# 3V3_MCU.net
KiCad netlist of a schematic drawn in Altium Designer
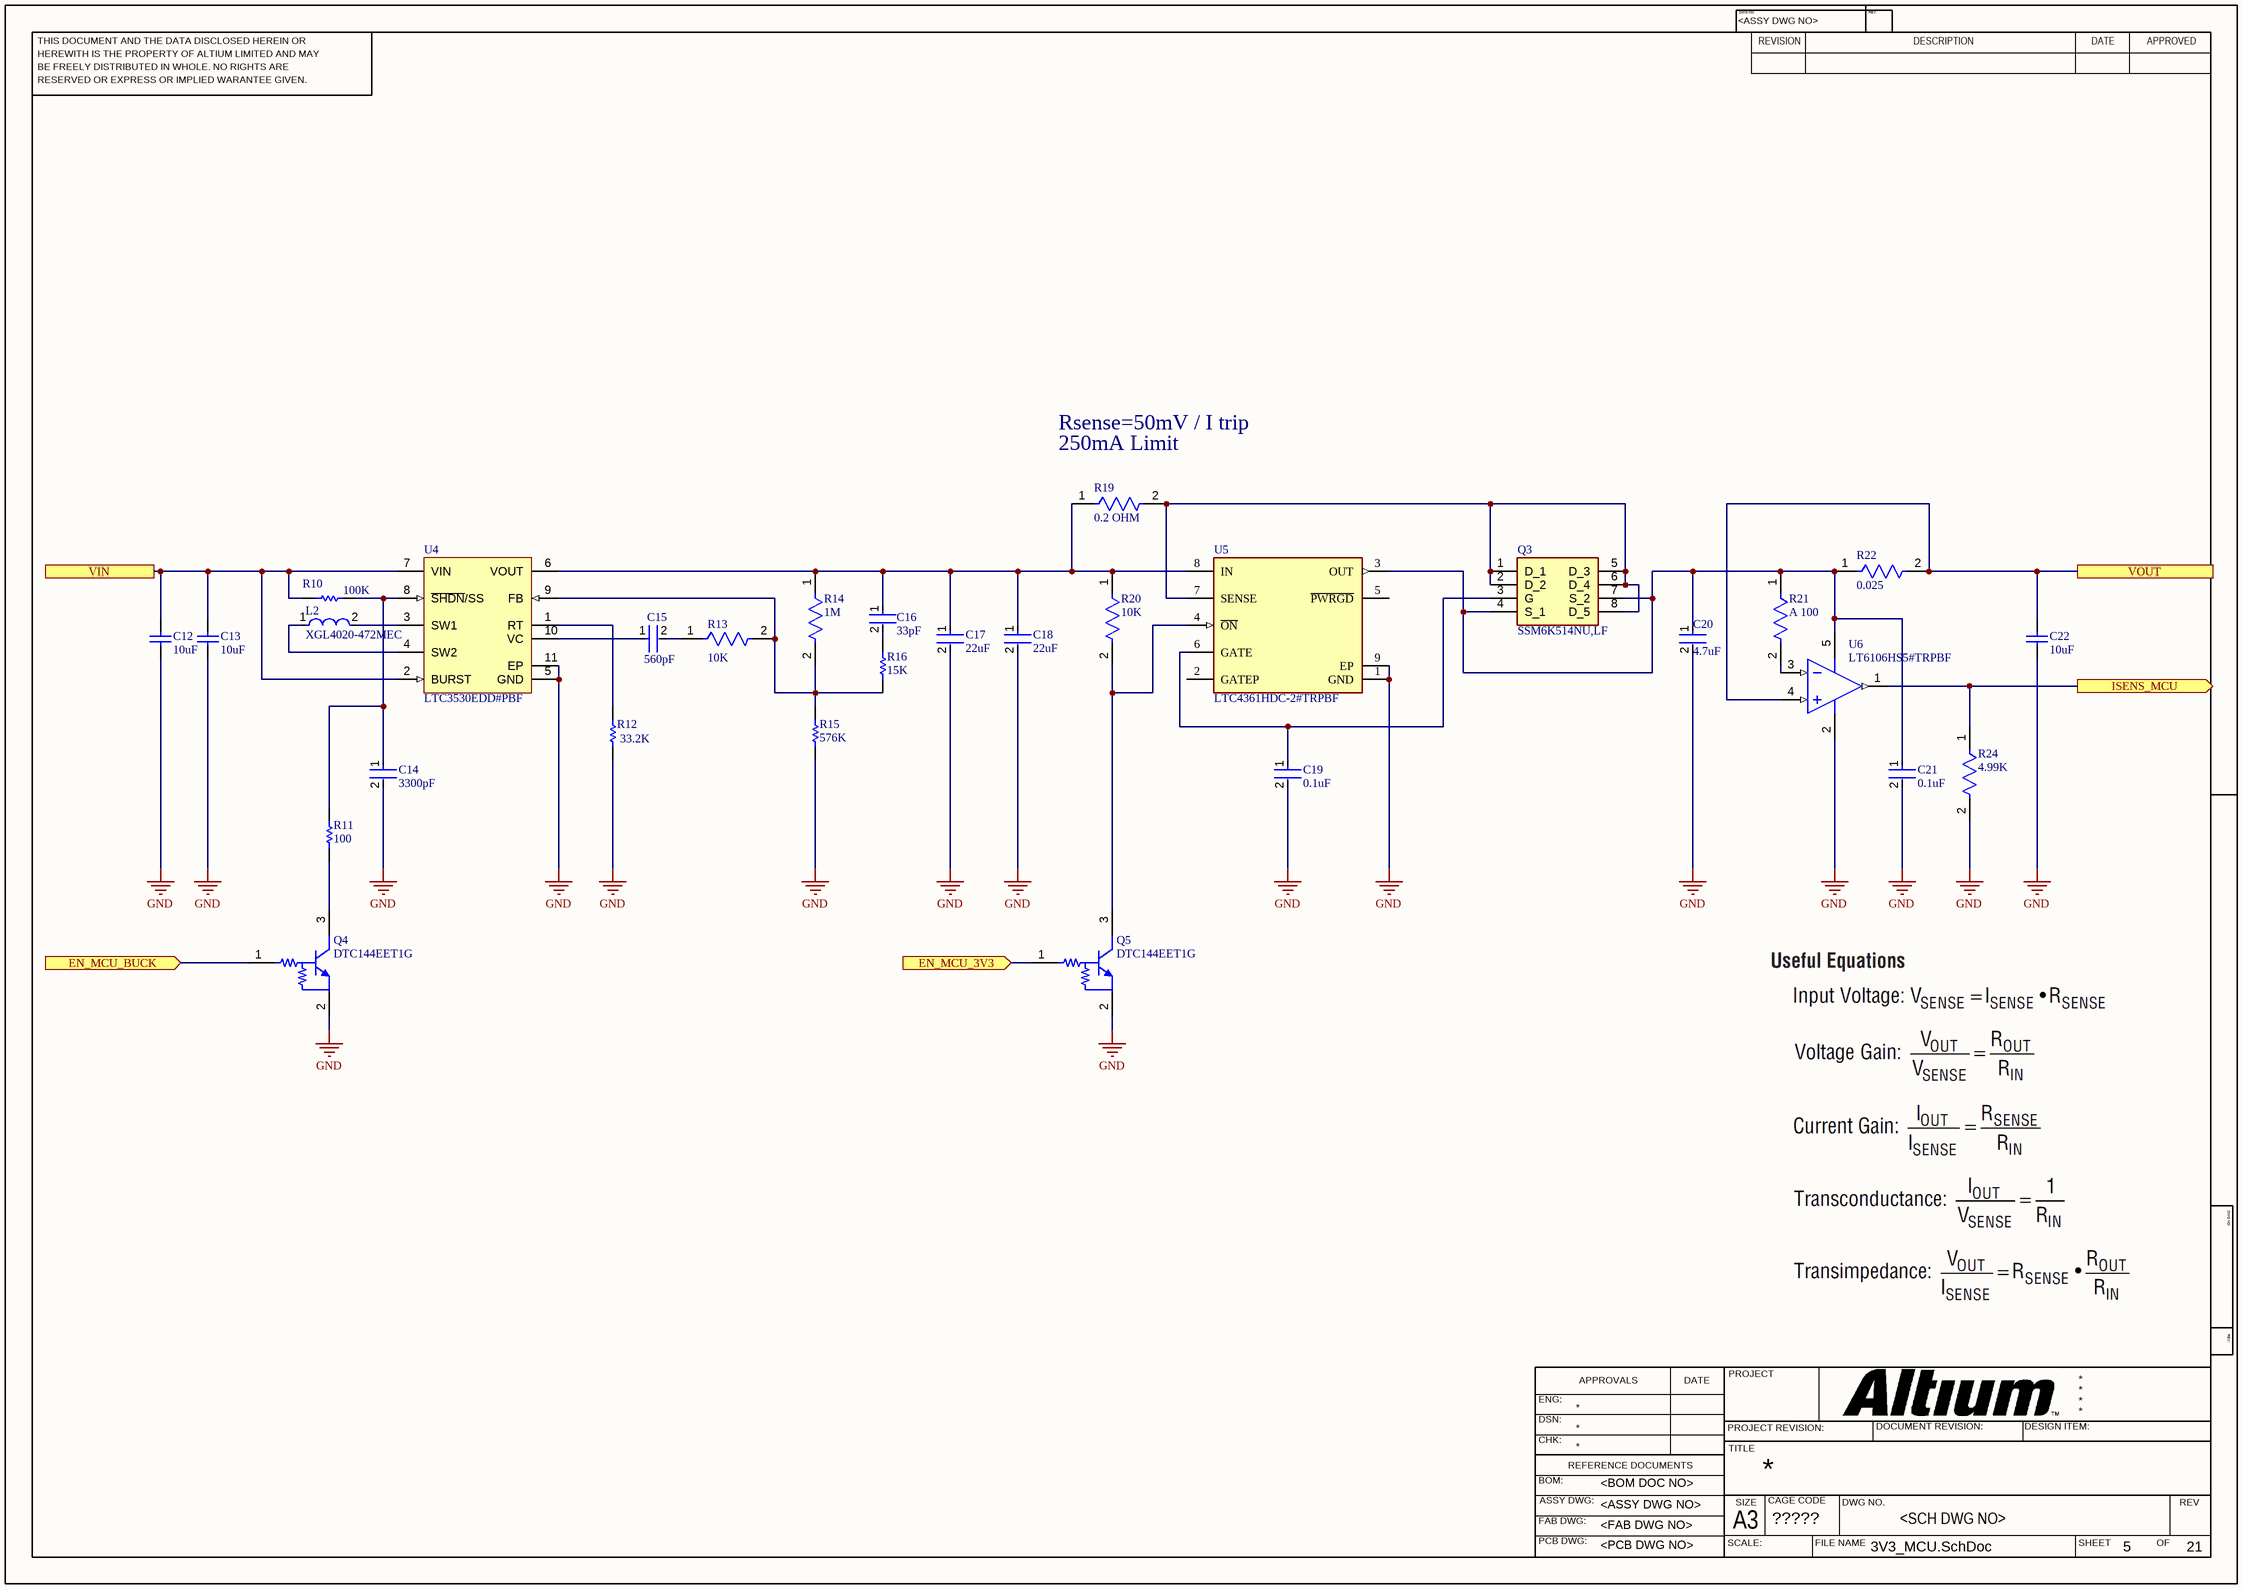
[diagram p0: 3V3_MCU.SchDoc]

(export (version "E")
  (design (tool "Eeschema 10.0.6"))
  (components
    (comp (ref "C12")
      (value "10uF")
      (footprint "CAPC2013X140X45NL15T25")
      (fields (field (name "PART NUMBER") "GRM21BR71A106KE51L") (field (name "MANUFACTURER") "Murata"))
      (libsource (lib "Altium Content Vault") (part "CAP"))
    )
    (comp (ref "C13")
      (value "10uF")
      (footprint "CAPC2013X140X45NL15T25")
      (fields (field (name "PART NUMBER") "GRM21BR71A106KE51L") (field (name "MANUFACTURER") "Murata"))
      (libsource (lib "Altium Content Vault") (part "CAP"))
    )
    (comp (ref "C14")
      (value "3300pF")
      (footprint "FP-C0603C-CF-MFG")
      (description "CAP CER 3300PF 50V 5% X7R 0603")
      (fields
        (field (name "MANUFACTURER PART NUMBER") "C0603C332J5RACTU")
        (field (name "MANUFACTURER") "KEMET")
      )
      (libsource (lib "Altium Content Vault") (part "b4654b650e69147ec39a6b967a45e02"))
    )
    (comp (ref "C15")
      (value "560pF")
      (footprint "FP-C0603C-CF-MFG")
      (description "CAP CER 560PF 50V X7R 0603")
      (fields
        (field (name "TOLERANCE") "0.1")
        (field (name "OCTOPART") "https://octopart.com/c0603c561k5ractu-kemet-138569")
      )
      (libsource (lib "Altium Content Vault") (part "b4654b650e69147ec39a6b967a45e02"))
    )
    (comp (ref "C16")
      (value "33pF")
      (footprint "FP-C0603C-CF-MFG")
      (description "CAP CER 33PF 16V X7R 0603")
      (fields
        (field (name "OCTOPART") "https://octopart.com/c0603c330k4rac7867-kemet-83501964")
        (field (name "MANUFACTURER PART NUMBER") "C0603C330K4RAC7867")
      )
      (libsource (lib "Altium Content Vault") (part "b4654b650e69147ec39a6b967a45e02"))
    )
    (comp (ref "C17")
      (value "22uF")
      (footprint "FP-GRM21B-0_2-e0_2_0_7-IPC_C")
      (description "Chip Multilayer Ceramic Capacitors for General Purpose, 0805, 22uF, X7T, +22%/-33%, 20%, 10V")
      (fields (field (name "VOLTAGE") "10V") (field (name "TOLERANCE") "20%"))
      (libsource (lib "Altium Content Vault") (part "b4654b650e69147ec39a6b967a45e02"))
    )
    (comp (ref "C18")
      (value "22uF")
      (footprint "FP-GRM21B-0_2-e0_2_0_7-IPC_C")
      (description "Chip Multilayer Ceramic Capacitors for General Purpose, 0805, 22uF, X7T, +22%/-33%, 20%, 10V")
      (fields (field (name "VOLTAGE") "10V") (field (name "TOLERANCE") "20%"))
      (libsource (lib "Altium Content Vault") (part "b4654b650e69147ec39a6b967a45e02"))
    )
    (comp (ref "C19")
      (value "0.1uF")
      (footprint "FP-C0603C-CF-MFG")
      (description "CAP CER 0.1UF 16V X7R 0603")
      (fields
        (field (name "OCTOPART") "https://octopart.com/c0603c104j4ractu-kemet-102515")
        (field (name "MANUFACTURER") "KEMET")
      )
      (libsource (lib "Altium Content Vault") (part "b4654b650e69147ec39a6b967a45e02"))
    )
    (comp (ref "C20")
      (value "4.7uF")
      (footprint "FP-GRM188-0_15-IPC_A")
      (description "CAP CER 4.7UF 10V X7S 0603")
      (fields (field (name "TOLERANCE") "10%"))
      (libsource (lib "Altium Content Vault") (part "02cd4be3c70576c341d710602a673aa"))
    )
    (comp (ref "C21")
      (value "0.1uF")
      (footprint "FP-C0603C-CF-MFG")
      (description "CAP CER 0.1UF 50V X7R 0603")
      (fields (field (name "TOLERANCE") "0.1") (field (name "MANUFACTURER") "KEMET"))
      (libsource (lib "Altium Content Vault") (part "b4654b650e69147ec39a6b967a45e02"))
    )
    (comp (ref "C22")
      (value "10uF")
      (footprint "CAPC2013X140X45NL15T25")
      (fields (field (name "PART NUMBER") "GRM21BR71A106KE51L") (field (name "MANUFACTURER") "Murata"))
      (libsource (lib "Altium Content Vault") (part "CAP"))
    )
    (comp (ref "L2")
      (value "XGL4020-472MEC")
      (footprint "FP-XGL4020-MFG")
      (description "Inductor, power, 4.7uH, SMT")
      (fields
        (field (name "MANUFACTURER") "Coilcraft")
        (field (name "OCTOPART") "https://octopart.com/xgl4020-472mec-coilcraft-99681031")
      )
      (libsource (lib "Altium Content Vault") (part "725321dda6339637d4d059423bc1c3c"))
    )
    (comp (ref "Q3")
      (value "SSM6K514NU,LF")
      (footprint "SamacSys:UDFN6B")
      (description "MOSFET (N-Channel)")
      (fields (field (name "MOUSER PART NUMBER") "757-SSM6K514NULF"))
      (libsource (lib "*") (part "SSM6K514NU,LF"))
    )
    (comp (ref "Q4")
      (value "DTC144EET1G")
      (footprint "ONSC-SC-75-3-463-01_V")
      (fields (field (name "MANUFACTURER") "On Semiconductor"))
      (libsource (lib "Altium Content Vault") (part "ONSC-BRT-NPN-B1E2C3-3"))
    )
    (comp (ref "Q5")
      (value "DTC144EET1G")
      (footprint "ONSC-SC-75-3-463-01_V")
      (fields (field (name "MANUFACTURER") "On Semiconductor"))
      (libsource (lib "Altium Content Vault") (part "ONSC-BRT-NPN-B1E2C3-3"))
    )
    (comp (ref "R10")
      (value "100K")
      (footprint "RESC1608X55X30ML20T10")
      (fields (field (name "PART NUMBER") "RK73B1JTTD104J") (field (name "MANUFACTURER") "KOA Speer"))
      (libsource (lib "Altium Content Vault") (part "RES"))
    )
    (comp (ref "R11")
      (value "100")
      (footprint "RESC1608X55X30LL20T10")
      (fields (field (name "MANUFACTURER") "KOA Speer") (field (name "PART NUMBER") "RK73B1JTTD101J"))
      (libsource (lib "Altium Content Vault") (part "RES"))
    )
    (comp (ref "R12")
      (value "33.2K")
      (footprint "RESC1608X55X30NL15T15")
      (fields (field (name "PART NUMBER") "ERJ-3EKF3322V") (field (name "MANUFACTURER") "Panasonic"))
      (libsource (lib "Altium Content Vault") (part "RES"))
    )
    (comp (ref "R13")
      (value "10K")
      (footprint "FP-RK73B1J-MFG")
      (description "RES 10K OHM 5% 1/10W 0603")
      (fields (field (name "TOLERANCE") "5%"))
      (libsource (lib "Altium Content Vault") (part "1029c3af85768c4190bb7ad29bc67b5"))
    )
    (comp (ref "R14")
      (value "1M")
      (footprint "FP-ERJ3EK-IPC_C")
      (description "RES SMD 1M OHM 1% 1/10W 0603")
      (fields (field (name "TOLERANCE") "1%"))
      (libsource (lib "Altium Content Vault") (part "1029c3af85768c4190bb7ad29bc67b5"))
    )
    (comp (ref "R15")
      (value "576K")
      (footprint "RESC1608X55X30LL15T15")
      (fields (field (name "PART NUMBER") "ERJ-3EKF5763V") (field (name "MANUFACTURER") "Panasonic"))
      (libsource (lib "Altium Content Vault") (part "RES"))
    )
    (comp (ref "R16")
      (value "15K")
      (footprint "RESC1608X55X30NL20T10")
      (fields (field (name "PART NUMBER") "RK73B1JTTD153J") (field (name "MANUFACTURER") "KOA Speer"))
      (libsource (lib "Altium Content Vault") (part "RES"))
    )
    (comp (ref "R19")
      (value "0.2 OHM")
      (footprint "FP-CSR0603-IPC_A")
      (description "General Purpose Thick Film Chip Resistor, 0603, 0.2Ω, 1%, 300ppm/°C, 0.125W")
      (fields (field (name "TOLERANCE") "1%"))
      (libsource (lib "Altium Content Vault") (part "1029c3af85768c4190bb7ad29bc67b5"))
    )
    (comp (ref "R20")
      (value "10K")
      (footprint "FP-RK73B1J-MFG")
      (description "RES 10K OHM 5% 1/10W 0603")
      (fields (field (name "TOLERANCE") "5%"))
      (libsource (lib "Altium Content Vault") (part "1029c3af85768c4190bb7ad29bc67b5"))
    )
    (comp (ref "R21")
      (value "A 100")
      (footprint "FP-ERA3A-IPC_B")
      (description "RES SMD 100 OHM 0.1% 1/10W 0603")
      (fields (field (name "TOLERANCE") "0.1%"))
      (libsource (lib "Altium Content Vault") (part "1029c3af85768c4190bb7ad29bc67b5"))
    )
    (comp (ref "R22")
      (value "0.025")
      (footprint "FP-PRL0816-MFG")
      (description "25 mOhms ±1% 0.33W Chip Resistor Wide 0306 (0816 Metric), Current Sense Thin Film")
      (fields (field (name "TOLERANCE") "1%"))
      (libsource (lib "Altium Content Vault") (part "1029c3af85768c4190bb7ad29bc67b5"))
    )
    (comp (ref "R24")
      (value "4.99K")
      (footprint "FP-ERA3A-IPC_C")
      (description "RES SMD 4.99KOHM 0.1% 1/10W 0603")
      (fields (field (name "TOLERANCE") "0.1%"))
      (libsource (lib "Altium Content Vault") (part "1029c3af85768c4190bb7ad29bc67b5"))
    )
    (comp (ref "U4")
      (value "LTC3530EDD#PBF")
      (footprint "LT-DD-10_V")
      (fields (field (name "MANUFACTURER") "Linear Technology"))
      (libsource (lib "Altium Content Vault") (part "LT-LTC3530-DD-10"))
    )
    (comp (ref "U5")
      (value "LTC4361HDC-2#TRPBF")
      (footprint "FP-DC8-8-05-08-1719-IPC_C")
      (description "IC OVP/OCP PROTECTION CTLR 8DFN")
      (libsource (lib "Altium Content Vault") (part "fbb45dfe5e09bf71f23ab0fd2a2f1dd"))
    )
    (comp (ref "U6")
      (value "LT6106HS5#TRPBF")
      (footprint "LT-S5-5-TSOT-23_M")
      (fields
        (field (name "MANUFACTURER") "Linear Technology")
        (field (name "LINEAR TECHNOLOGY PART NUMBER") "LT6106")
      )
      (libsource (lib "Altium Content Vault") (part "LT-LT6106-LTC6101HV-5"))
    )
  )
  (nets
    (net (code "1") (name "/EN_MCU_3V3") (class "Default")
      (node (ref "Q5") (pin "1") (pinfunction "B_1") (pintype "passive"))
    )
    (net (code "2") (name "/EN_MCU_BUCK") (class "Default")
      (node (ref "Q4") (pin "1") (pinfunction "B_1") (pintype "passive"))
    )
    (net (code "3") (name "/ISENS_MCU") (class "Default")
      (node (ref "R24") (pin "1") (pinfunction "1_1") (pintype "passive"))
      (node (ref "U6") (pin "1") (pinfunction "OUT_1") (pintype "output"))
    )
    (net (code "4") (name "/VIN") (class "Default")
      (node (ref "C12") (pin "2") (pinfunction "2_2") (pintype "passive"))
      (node (ref "C13") (pin "2") (pinfunction "2_2") (pintype "passive"))
      (node (ref "R10") (pin "2") (pinfunction "2_2") (pintype "passive"))
      (node (ref "U4") (pin "2") (pinfunction "BURST_2") (pintype "input"))
      (node (ref "U4") (pin "7") (pinfunction "VIN_7") (pintype "power_in"))
    )
    (net (code "5") (name "/VOUT") (class "Default")
      (node (ref "C22") (pin "2") (pinfunction "2_2") (pintype "passive"))
      (node (ref "R22") (pin "2") (pinfunction "2_2") (pintype "passive"))
      (node (ref "U6") (pin "4") (pinfunction "+IN_4") (pintype "input"))
    )
    (net (code "6") (name "GND") (class "Default")
      (node (ref "C12") (pin "1") (pinfunction "1_1") (pintype "passive"))
      (node (ref "C13") (pin "1") (pinfunction "1_1") (pintype "passive"))
      (node (ref "C14") (pin "2") (pinfunction "2_2") (pintype "passive"))
      (node (ref "C17") (pin "2") (pinfunction "2_2") (pintype "passive"))
      (node (ref "C18") (pin "2") (pinfunction "2_2") (pintype "passive"))
      (node (ref "C19") (pin "2") (pinfunction "2_2") (pintype "passive"))
      (node (ref "C20") (pin "2") (pinfunction "2_2") (pintype "passive"))
      (node (ref "C21") (pin "2") (pinfunction "2_2") (pintype "passive"))
      (node (ref "C22") (pin "1") (pinfunction "1_1") (pintype "passive"))
      (node (ref "Q4") (pin "2") (pinfunction "E_2") (pintype "passive"))
      (node (ref "Q5") (pin "2") (pinfunction "E_2") (pintype "passive"))
      (node (ref "R12") (pin "1") (pinfunction "1_1") (pintype "passive"))
      (node (ref "R15") (pin "1") (pinfunction "1_1") (pintype "passive"))
      (node (ref "R24") (pin "2") (pinfunction "2_2") (pintype "passive"))
      (node (ref "U4") (pin "11") (pinfunction "EP_11") (pintype "power_in"))
      (node (ref "U4") (pin "5") (pinfunction "GND_5") (pintype "power_in"))
      (node (ref "U5") (pin "1") (pinfunction "GND_1") (pintype "power_in"))
      (node (ref "U5") (pin "9") (pinfunction "EP_9") (pintype "power_in"))
      (node (ref "U6") (pin "2") (pinfunction "V-_2") (pintype "power_in"))
    )
    (net (code "7") (name "Net-(C15-Pad2)") (class "Default")
      (node (ref "C15") (pin "2") (pinfunction "2_2") (pintype "passive"))
      (node (ref "R13") (pin "1") (pinfunction "1_1") (pintype "passive"))
    )
    (net (code "8") (name "Net-(C16-Pad2)") (class "Default")
      (node (ref "C16") (pin "2") (pinfunction "2_2") (pintype "passive"))
      (node (ref "R16") (pin "2") (pinfunction "2_2") (pintype "passive"))
    )
    (net (code "9") (name "Net-(Q3-D_1)") (class "Default")
      (node (ref "Q3") (pin "1") (pinfunction "D_1_1") (pintype "passive"))
      (node (ref "Q3") (pin "2") (pinfunction "D_2_2") (pintype "passive"))
      (node (ref "Q3") (pin "5") (pinfunction "D_3_5") (pintype "passive"))
      (node (ref "Q3") (pin "6") (pinfunction "D_4_6") (pintype "passive"))
      (node (ref "Q3") (pin "8") (pinfunction "D_5_8") (pintype "passive"))
      (node (ref "R19") (pin "2") (pinfunction "2_2") (pintype "passive"))
      (node (ref "U5") (pin "7") (pinfunction "SENSE_7") (pintype "passive"))
    )
    (net (code "10") (name "Net-(Q3-G)") (class "Default")
      (node (ref "C19") (pin "1") (pinfunction "1_1") (pintype "passive"))
      (node (ref "Q3") (pin "3") (pinfunction "G_3") (pintype "passive"))
      (node (ref "U5") (pin "6") (pinfunction "GATE_6") (pintype "passive"))
    )
    (net (code "11") (name "Net-(Q3-S_1)") (class "Default")
      (node (ref "C20") (pin "1") (pinfunction "1_1") (pintype "passive"))
      (node (ref "C21") (pin "1") (pinfunction "1_1") (pintype "passive"))
      (node (ref "Q3") (pin "4") (pinfunction "S_1_4") (pintype "passive"))
      (node (ref "Q3") (pin "7") (pinfunction "S_2_7") (pintype "passive"))
      (node (ref "R21") (pin "1") (pinfunction "1_1") (pintype "passive"))
      (node (ref "R22") (pin "1") (pinfunction "1_1") (pintype "passive"))
      (node (ref "U5") (pin "3") (pinfunction "OUT_3") (pintype "output"))
      (node (ref "U6") (pin "5") (pinfunction "V+_5") (pintype "power_in"))
    )
    (net (code "12") (name "Net-(Q4-C)") (class "Default")
      (node (ref "Q4") (pin "3") (pinfunction "C_3") (pintype "passive"))
      (node (ref "R11") (pin "1") (pinfunction "1_1") (pintype "passive"))
    )
    (net (code "13") (name "Net-(Q5-C)") (class "Default")
      (node (ref "Q5") (pin "3") (pinfunction "C_3") (pintype "passive"))
      (node (ref "R20") (pin "2") (pinfunction "2_2") (pintype "passive"))
      (node (ref "U5") (pin "4") (pinfunction "~{ON}_4") (pintype "input"))
    )
    (net (code "14") (name "Net-(U4-FB)") (class "Default")
      (node (ref "R13") (pin "2") (pinfunction "2_2") (pintype "passive"))
      (node (ref "R14") (pin "2") (pinfunction "2_2") (pintype "passive"))
      (node (ref "R15") (pin "2") (pinfunction "2_2") (pintype "passive"))
      (node (ref "R16") (pin "1") (pinfunction "1_1") (pintype "passive"))
      (node (ref "U4") (pin "9") (pinfunction "FB_9") (pintype "input"))
    )
    (net (code "15") (name "Net-(U4-RT)") (class "Default")
      (node (ref "R12") (pin "2") (pinfunction "2_2") (pintype "passive"))
      (node (ref "U4") (pin "1") (pinfunction "RT_1") (pintype "passive"))
    )
    (net (code "16") (name "Net-(U4-SW1)") (class "Default")
      (node (ref "L2") (pin "2") (pinfunction "2_2") (pintype "passive"))
      (node (ref "U4") (pin "3") (pinfunction "SW1_3") (pintype "passive"))
    )
    (net (code "17") (name "Net-(U4-SW2)") (class "Default")
      (node (ref "L2") (pin "1") (pinfunction "1_1") (pintype "passive"))
      (node (ref "U4") (pin "4") (pinfunction "SW2_4") (pintype "passive"))
    )
    (net (code "18") (name "Net-(U4-VC)") (class "Default")
      (node (ref "C15") (pin "1") (pinfunction "1_1") (pintype "passive"))
      (node (ref "U4") (pin "10") (pinfunction "VC_10") (pintype "passive"))
    )
    (net (code "19") (name "Net-(U4-VOUT)") (class "Default")
      (node (ref "C16") (pin "1") (pinfunction "1_1") (pintype "passive"))
      (node (ref "C17") (pin "1") (pinfunction "1_1") (pintype "passive"))
      (node (ref "C18") (pin "1") (pinfunction "1_1") (pintype "passive"))
      (node (ref "R14") (pin "1") (pinfunction "1_1") (pintype "passive"))
      (node (ref "R19") (pin "1") (pinfunction "1_1") (pintype "passive"))
      (node (ref "R20") (pin "1") (pinfunction "1_1") (pintype "passive"))
      (node (ref "U4") (pin "6") (pinfunction "VOUT_6") (pintype "power_in"))
      (node (ref "U5") (pin "8") (pinfunction "IN_8") (pintype "power_in"))
    )
    (net (code "20") (name "Net-(U4-~{SHDN}{slash}SS)") (class "Default")
      (node (ref "C14") (pin "1") (pinfunction "1_1") (pintype "passive"))
      (node (ref "R10") (pin "1") (pinfunction "1_1") (pintype "passive"))
      (node (ref "R11") (pin "2") (pinfunction "2_2") (pintype "passive"))
      (node (ref "U4") (pin "8") (pinfunction "~{SHDN}/SS_8") (pintype "input"))
    )
    (net (code "21") (name "Net-(U6--IN)") (class "Default")
      (node (ref "R21") (pin "2") (pinfunction "2_2") (pintype "passive"))
      (node (ref "U6") (pin "3") (pinfunction "-IN_3") (pintype "input"))
    )
    (net (code "22") (name "unconnected-(U5-GATEP-Pad2)") (class "Default")
      (node (ref "U5") (pin "2") (pinfunction "GATEP_2") (pintype "passive"))
    )
    (net (code "23") (name "unconnected-(U5-~{PWRGD}-Pad5)") (class "Default")
      (node (ref "U5") (pin "5") (pinfunction "~{PWRGD}_5") (pintype "open_collector"))
    )
  )
)
